# encoder.net
KiCad netlist of a schematic drawn in Altium Designer
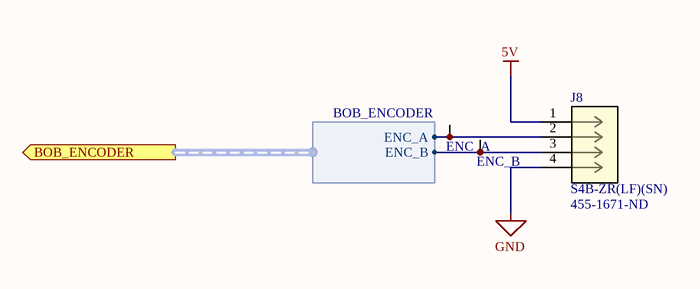
[diagram p0: encoder.SchDoc]

(export (version "E")
  (design (tool "Eeschema 10.0.6"))
  (components
    (comp (ref "ENC_A")
      (value "Test Point (Via)")
      (footprint "TP")
      (libsource (lib "AltiumLibraries") (part "Test Point (Via)"))
    )
    (comp (ref "ENC_B")
      (value "Test Point (Via)")
      (footprint "TP")
      (libsource (lib "AltiumLibraries") (part "Test Point (Via)"))
    )
    (comp (ref "J8")
      (value "S4B-ZR(LF)(SN)")
      (footprint "CN S4B-ZR(LF)(SN)_JST")
      (description "Connector Header Through Hole, Right Angle 4 position 0.059\" (1.50mm)")
      (fields
        (field (name "SUPPLIER PART NUMBER 1") "455-1671-ND")
        (field (name "COPYRIGHT") "Copyright (C) 2021 Ultra Librarian. All rights reserved.")
      )
      (libsource (lib "AltiumLibraries") (part "CN HDR 4POS JST ZR"))
    )
  )
  (nets
    (net (code "3") (name "5V") (class "Default")
      (node (ref "J8") (pin "1") (pinfunction "1_1") (pintype "passive"))
    )
    (net (code "4") (name "GND") (class "Default")
      (node (ref "J8") (pin "4") (pinfunction "4_4") (pintype "passive"))
    )
    (net (code "5") (name "Net-(ENC_A-Pad1)") (class "Default")
      (node (ref "ENC_A") (pin "1") (pinfunction "1_1") (pintype "passive"))
      (node (ref "J8") (pin "2") (pinfunction "2_2") (pintype "passive"))
    )
    (net (code "6") (name "Net-(ENC_B-Pad1)") (class "Default")
      (node (ref "ENC_B") (pin "1") (pinfunction "1_1") (pintype "passive"))
      (node (ref "J8") (pin "3") (pinfunction "3_3") (pintype "passive"))
    )
  )
)
